# radio.net
KiCad netlist of a schematic drawn in Altium Designer
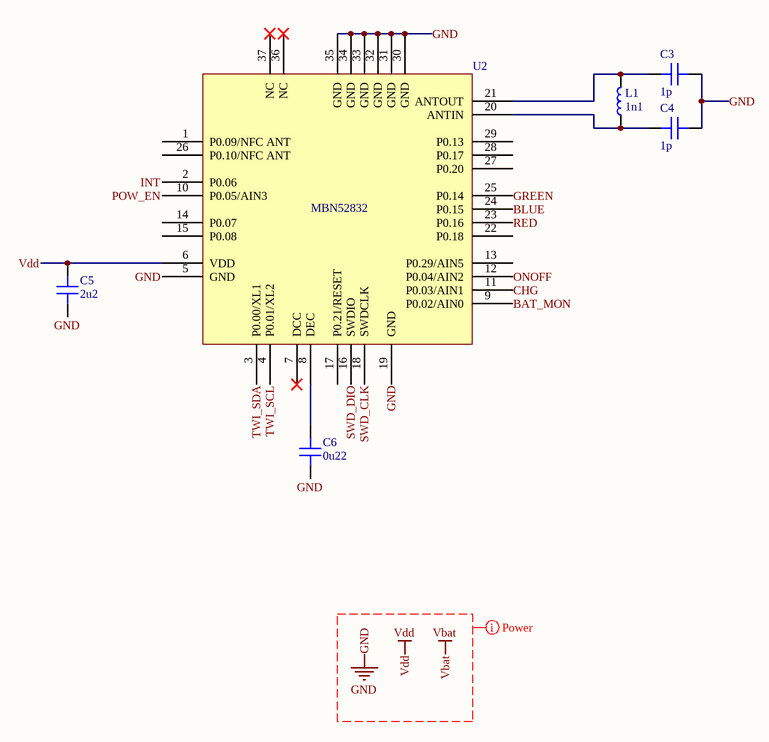
[diagram p0: radio.SchDoc]

(export (version "E")
  (design (tool "Eeschema 10.0.6"))
  (components
    (comp (ref "C3")
      (value "1p")
      (footprint "CAP 0201/0603")
      (description "CAP CER 0201 1pF 50V ±0.1pF C0G")
      (fields (field (name "PART NUMBER") "GRM0335C1H1R0BA01D") (field (name "MANUFACTURER") "Murata"))
      (libsource (lib "ekuore-library") (part "Capacitor"))
    )
    (comp (ref "C4")
      (value "1p")
      (footprint "CAP 0201/0603")
      (description "CAP CER 0201 1pF 50V ±0.1pF C0G")
      (fields (field (name "PART NUMBER") "GRM0335C1H1R0BA01D") (field (name "MANUFACTURER") "Murata"))
      (libsource (lib "ekuore-library") (part "Capacitor"))
    )
    (comp (ref "C5")
      (value "2u2")
      (footprint "CAP 0402/1005")
      (description "CAP CER 0402 2.2uF 16V 10% X5R")
      (fields (field (name "PART NUMBER") "GRM155R61C225KE11D") (field (name "MANUFACTURER") "Murata"))
      (libsource (lib "ekuore-library") (part "Capacitor"))
    )
    (comp (ref "C6")
      (value "0u22")
      (footprint "CAP 0201/0603")
      (description "CAP CER 0201 0.22uF 10V 10% X5R")
      (fields (field (name "PART NUMBER") "GRM033R61A224KE90D") (field (name "MANUFACTURER") "Murata"))
      (libsource (lib "ekuore-library") (part "Capacitor"))
    )
    (comp (ref "L1")
      (value "1n1")
      (footprint "FER 0201/0603")
      (description "IND 0201 1.1nH +-0.1nH 0.75A 0.1R")
      (fields (field (name "PART NUMBER") "LQP03TN1N1B02D") (field (name "MANUFACTURER") "Murata"))
      (libsource (lib "ekuore-library") (part "Inductor"))
    )
    (comp (ref "U2")
      (value "MBN52832")
      (footprint "Murata MBN52832")
      (description "Bluetooth v5.0 (BLE) SMART SOC IoT/NFC 1Mbps 3.3V")
      (fields (field (name "PART NUMBER") "WSM-BL241-ADA-008") (field (name "MANUFACTURER") "Murata"))
      (libsource (lib "ekuore-library") (part "Murata MBN52832"))
    )
  )
  (nets
    (net (code "1") (name "/BAT_MON") (class "Default")
      (node (ref "U2") (pin "9") (pinfunction "P0.02/AIN0_9") (pintype "passive"))
    )
    (net (code "2") (name "/BLUE") (class "Default")
      (node (ref "U2") (pin "24") (pinfunction "P0.15_24") (pintype "passive"))
    )
    (net (code "3") (name "/CHG") (class "Default")
      (node (ref "U2") (pin "11") (pinfunction "P0.03/AIN1_11") (pintype "passive"))
    )
    (net (code "4") (name "/GREEN") (class "Default")
      (node (ref "U2") (pin "25") (pinfunction "P0.14_25") (pintype "passive"))
    )
    (net (code "5") (name "/INT") (class "Default")
      (node (ref "U2") (pin "2") (pinfunction "P0.06_2") (pintype "passive"))
    )
    (net (code "6") (name "/ONOFF") (class "Default")
      (node (ref "U2") (pin "12") (pinfunction "P0.04/AIN2_12") (pintype "passive"))
    )
    (net (code "7") (name "/POW_EN") (class "Default")
      (node (ref "U2") (pin "10") (pinfunction "P0.05/AIN3_10") (pintype "passive"))
    )
    (net (code "8") (name "/RED") (class "Default")
      (node (ref "U2") (pin "23") (pinfunction "P0.16_23") (pintype "passive"))
    )
    (net (code "9") (name "/SWD_CLK") (class "Default")
      (node (ref "U2") (pin "18") (pinfunction "SWDCLK_18") (pintype "passive"))
    )
    (net (code "10") (name "/SWD_DIO") (class "Default")
      (node (ref "U2") (pin "16") (pinfunction "SWDIO_16") (pintype "passive"))
    )
    (net (code "11") (name "/TWI_SCL") (class "Default")
      (node (ref "U2") (pin "4") (pinfunction "P0.01/XL2_4") (pintype "passive"))
    )
    (net (code "12") (name "/TWI_SDA") (class "Default")
      (node (ref "U2") (pin "3") (pinfunction "P0.00/XL1_3") (pintype "passive"))
    )
    (net (code "13") (name "GND") (class "Default")
      (node (ref "C3") (pin "2") (pinfunction "2_2") (pintype "passive"))
      (node (ref "C4") (pin "2") (pinfunction "2_2") (pintype "passive"))
      (node (ref "C5") (pin "1") (pinfunction "1_1") (pintype "passive"))
      (node (ref "C6") (pin "1") (pinfunction "1_1") (pintype "passive"))
      (node (ref "U2") (pin "19") (pinfunction "GND_19") (pintype "passive"))
      (node (ref "U2") (pin "30") (pinfunction "GND_30") (pintype "passive"))
      (node (ref "U2") (pin "31") (pinfunction "GND_31") (pintype "passive"))
      (node (ref "U2") (pin "32") (pinfunction "GND_32") (pintype "passive"))
      (node (ref "U2") (pin "33") (pinfunction "GND_33") (pintype "passive"))
      (node (ref "U2") (pin "34") (pinfunction "GND_34") (pintype "passive"))
      (node (ref "U2") (pin "35") (pinfunction "GND_35") (pintype "passive"))
      (node (ref "U2") (pin "5") (pinfunction "GND_5") (pintype "passive"))
    )
    (net (code "14") (name "Net-(U2-ANTIN)") (class "Default")
      (node (ref "C4") (pin "1") (pinfunction "1_1") (pintype "passive"))
      (node (ref "L1") (pin "1") (pinfunction "1_1") (pintype "passive"))
      (node (ref "U2") (pin "20") (pinfunction "ANTIN_20") (pintype "passive"))
    )
    (net (code "15") (name "Net-(U2-ANTOUT)") (class "Default")
      (node (ref "C3") (pin "1") (pinfunction "1_1") (pintype "passive"))
      (node (ref "L1") (pin "2") (pinfunction "2_2") (pintype "passive"))
      (node (ref "U2") (pin "21") (pinfunction "ANTOUT_21") (pintype "passive"))
    )
    (net (code "16") (name "Net-(U2-DEC)") (class "Default")
      (node (ref "C6") (pin "2") (pinfunction "2_2") (pintype "passive"))
      (node (ref "U2") (pin "8") (pinfunction "DEC_8") (pintype "passive"))
    )
    (net (code "18") (name "Vdd") (class "Default")
      (node (ref "C5") (pin "2") (pinfunction "2_2") (pintype "passive"))
      (node (ref "U2") (pin "6") (pinfunction "VDD_6") (pintype "passive"))
    )
    (net (code "19") (name "unconnected-(U2-DCC-Pad7)") (class "Default")
      (node (ref "U2") (pin "7") (pinfunction "DCC_7") (pintype "passive+no_connect"))
    )
    (net (code "20") (name "unconnected-(U2-NC-Pad36)") (class "Default")
      (node (ref "U2") (pin "36") (pinfunction "NC_36") (pintype "passive+no_connect"))
    )
    (net (code "21") (name "unconnected-(U2-NC-Pad37)") (class "Default")
      (node (ref "U2") (pin "37") (pinfunction "NC_37") (pintype "passive+no_connect"))
    )
    (net (code "22") (name "unconnected-(U2-P0.07-Pad14)") (class "Default")
      (node (ref "U2") (pin "14") (pinfunction "P0.07_14") (pintype "passive"))
    )
    (net (code "23") (name "unconnected-(U2-P0.08-Pad15)") (class "Default")
      (node (ref "U2") (pin "15") (pinfunction "P0.08_15") (pintype "passive"))
    )
    (net (code "24") (name "unconnected-(U2-P0.09{slash}NFC_ANT-Pad1)") (class "Default")
      (node (ref "U2") (pin "1") (pinfunction "P0.09/NFC_ANT_1") (pintype "passive"))
    )
    (net (code "25") (name "unconnected-(U2-P0.10{slash}NFC_ANT-Pad26)") (class "Default")
      (node (ref "U2") (pin "26") (pinfunction "P0.10/NFC_ANT_26") (pintype "passive"))
    )
    (net (code "26") (name "unconnected-(U2-P0.13-Pad29)") (class "Default")
      (node (ref "U2") (pin "29") (pinfunction "P0.13_29") (pintype "passive"))
    )
    (net (code "27") (name "unconnected-(U2-P0.17-Pad28)") (class "Default")
      (node (ref "U2") (pin "28") (pinfunction "P0.17_28") (pintype "passive"))
    )
    (net (code "28") (name "unconnected-(U2-P0.18-Pad22)") (class "Default")
      (node (ref "U2") (pin "22") (pinfunction "P0.18_22") (pintype "passive"))
    )
    (net (code "29") (name "unconnected-(U2-P0.20-Pad27)") (class "Default")
      (node (ref "U2") (pin "27") (pinfunction "P0.20_27") (pintype "passive"))
    )
    (net (code "30") (name "unconnected-(U2-P0.21{slash}RESET-Pad17)") (class "Default")
      (node (ref "U2") (pin "17") (pinfunction "P0.21/RESET_17") (pintype "passive"))
    )
    (net (code "31") (name "unconnected-(U2-P0.29{slash}AIN5-Pad13)") (class "Default")
      (node (ref "U2") (pin "13") (pinfunction "P0.29/AIN5_13") (pintype "passive"))
    )
  )
)
